# Nucleo.net
KiCad netlist of a schematic drawn in Altium Designer
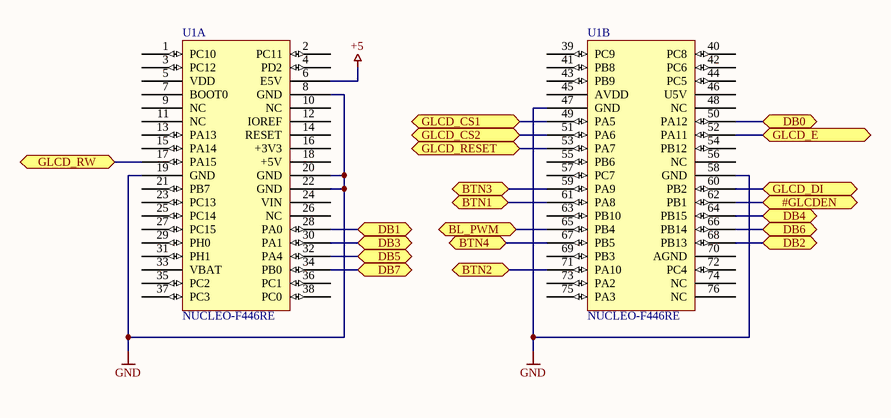
[diagram p0: Nucleo.SchDoc]

(export (version "E")
  (design (tool "Eeschema 10.0.6"))
  (components
    (comp (ref "U1")
      (value "NUCLEO-F446RE")
      (footprint "FP_NUCLEO-64_2x20")
      (libsource (lib "hallglib") (part "NUCLEO-F446RE"))
    )
  )
  (nets
    (net (code "1") (name "+5") (class "Default")
      (node (ref "U1") (pin "6") (pinfunction "E5V_6") (pintype "power_in"))
    )
    (net (code "2") (name "/#GLCDEN") (class "Default")
      (node (ref "U1") (pin "62") (pinfunction "PB1_62") (pintype "bidirectional"))
    )
    (net (code "3") (name "/BL_PWM") (class "Default")
      (node (ref "U1") (pin "65") (pinfunction "PB4_65") (pintype "bidirectional"))
    )
    (net (code "4") (name "/BTN1") (class "Default")
      (node (ref "U1") (pin "61") (pinfunction "PA8_61") (pintype "bidirectional"))
    )
    (net (code "5") (name "/BTN2") (class "Default")
      (node (ref "U1") (pin "71") (pinfunction "PA10_71") (pintype "bidirectional"))
    )
    (net (code "6") (name "/BTN3") (class "Default")
      (node (ref "U1") (pin "59") (pinfunction "PA9_59") (pintype "bidirectional"))
    )
    (net (code "7") (name "/BTN4") (class "Default")
      (node (ref "U1") (pin "67") (pinfunction "PB5_67") (pintype "bidirectional"))
    )
    (net (code "8") (name "/DB0") (class "Default")
      (node (ref "U1") (pin "50") (pinfunction "PA12_50") (pintype "bidirectional"))
    )
    (net (code "9") (name "/DB1") (class "Default")
      (node (ref "U1") (pin "28") (pinfunction "PA0_28") (pintype "bidirectional"))
    )
    (net (code "10") (name "/DB2") (class "Default")
      (node (ref "U1") (pin "68") (pinfunction "PB13_68") (pintype "bidirectional"))
    )
    (net (code "11") (name "/DB3") (class "Default")
      (node (ref "U1") (pin "30") (pinfunction "PA1_30") (pintype "bidirectional"))
    )
    (net (code "12") (name "/DB4") (class "Default")
      (node (ref "U1") (pin "64") (pinfunction "PB15_64") (pintype "bidirectional"))
    )
    (net (code "13") (name "/DB5") (class "Default")
      (node (ref "U1") (pin "32") (pinfunction "PA4_32") (pintype "bidirectional"))
    )
    (net (code "14") (name "/DB6") (class "Default")
      (node (ref "U1") (pin "66") (pinfunction "PB14_66") (pintype "bidirectional"))
    )
    (net (code "15") (name "/DB7") (class "Default")
      (node (ref "U1") (pin "34") (pinfunction "PB0_34") (pintype "bidirectional"))
    )
    (net (code "16") (name "/GLCD_CS1") (class "Default")
      (node (ref "U1") (pin "49") (pinfunction "PA5_49") (pintype "bidirectional"))
    )
    (net (code "17") (name "/GLCD_CS2") (class "Default")
      (node (ref "U1") (pin "51") (pinfunction "PA6_51") (pintype "bidirectional"))
    )
    (net (code "18") (name "/GLCD_DI") (class "Default")
      (node (ref "U1") (pin "60") (pinfunction "PB2_60") (pintype "bidirectional"))
    )
    (net (code "19") (name "/GLCD_E") (class "Default")
      (node (ref "U1") (pin "52") (pinfunction "PA11_52") (pintype "bidirectional"))
    )
    (net (code "20") (name "/GLCD_RESET") (class "Default")
      (node (ref "U1") (pin "53") (pinfunction "PA7_53") (pintype "bidirectional"))
    )
    (net (code "21") (name "/GLCD_RW") (class "Default")
      (node (ref "U1") (pin "17") (pinfunction "PA15_17") (pintype "bidirectional"))
    )
    (net (code "22") (name "GND") (class "Default")
      (node (ref "U1") (pin "19") (pinfunction "GND_19") (pintype "passive"))
      (node (ref "U1") (pin "20") (pinfunction "GND_20") (pintype "passive"))
      (node (ref "U1") (pin "22") (pinfunction "GND_22") (pintype "passive"))
      (node (ref "U1") (pin "47") (pinfunction "GND_47") (pintype "passive"))
      (node (ref "U1") (pin "58") (pinfunction "GND_58") (pintype "passive"))
      (node (ref "U1") (pin "8") (pinfunction "GND_8") (pintype "passive"))
    )
    (net (code "23") (name "unconnected-(U1A-+3V3-Pad16)") (class "Default")
      (node (ref "U1") (pin "16") (pinfunction "+3V3_16") (pintype "power_in"))
    )
    (net (code "24") (name "unconnected-(U1A-+5V-Pad18)") (class "Default")
      (node (ref "U1") (pin "18") (pinfunction "+5V_18") (pintype "power_in"))
    )
    (net (code "25") (name "unconnected-(U1A-BOOT0-Pad7)") (class "Default")
      (node (ref "U1") (pin "7") (pinfunction "BOOT0_7") (pintype "passive"))
    )
    (net (code "26") (name "unconnected-(U1A-IOREF-Pad12)") (class "Default")
      (node (ref "U1") (pin "12") (pinfunction "IOREF_12") (pintype "passive"))
    )
    (net (code "27") (name "unconnected-(U1A-NC-Pad9)") (class "Default")
      (node (ref "U1") (pin "9") (pinfunction "NC_9") (pintype "passive"))
    )
    (net (code "28") (name "unconnected-(U1A-NC-Pad10)") (class "Default")
      (node (ref "U1") (pin "10") (pinfunction "NC_10") (pintype "passive"))
    )
    (net (code "29") (name "unconnected-(U1A-NC-Pad11)") (class "Default")
      (node (ref "U1") (pin "11") (pinfunction "NC_11") (pintype "passive"))
    )
    (net (code "30") (name "unconnected-(U1A-NC-Pad26)") (class "Default")
      (node (ref "U1") (pin "26") (pinfunction "NC_26") (pintype "passive"))
    )
    (net (code "31") (name "unconnected-(U1A-PA13-Pad13)") (class "Default")
      (node (ref "U1") (pin "13") (pinfunction "PA13_13") (pintype "bidirectional"))
    )
    (net (code "32") (name "unconnected-(U1A-PA14-Pad15)") (class "Default")
      (node (ref "U1") (pin "15") (pinfunction "PA14_15") (pintype "bidirectional"))
    )
    (net (code "33") (name "unconnected-(U1A-PB7-Pad21)") (class "Default")
      (node (ref "U1") (pin "21") (pinfunction "PB7_21") (pintype "bidirectional"))
    )
    (net (code "34") (name "unconnected-(U1A-PC0-Pad38)") (class "Default")
      (node (ref "U1") (pin "38") (pinfunction "PC0_38") (pintype "bidirectional"))
    )
    (net (code "35") (name "unconnected-(U1A-PC1-Pad36)") (class "Default")
      (node (ref "U1") (pin "36") (pinfunction "PC1_36") (pintype "bidirectional"))
    )
    (net (code "36") (name "unconnected-(U1A-PC2-Pad35)") (class "Default")
      (node (ref "U1") (pin "35") (pinfunction "PC2_35") (pintype "bidirectional"))
    )
    (net (code "37") (name "unconnected-(U1A-PC3-Pad37)") (class "Default")
      (node (ref "U1") (pin "37") (pinfunction "PC3_37") (pintype "bidirectional"))
    )
    (net (code "38") (name "unconnected-(U1A-PC10-Pad1)") (class "Default")
      (node (ref "U1") (pin "1") (pinfunction "PC10_1") (pintype "bidirectional"))
    )
    (net (code "39") (name "unconnected-(U1A-PC11-Pad2)") (class "Default")
      (node (ref "U1") (pin "2") (pinfunction "PC11_2") (pintype "bidirectional"))
    )
    (net (code "40") (name "unconnected-(U1A-PC12-Pad3)") (class "Default")
      (node (ref "U1") (pin "3") (pinfunction "PC12_3") (pintype "bidirectional"))
    )
    (net (code "41") (name "unconnected-(U1A-PC13-Pad23)") (class "Default")
      (node (ref "U1") (pin "23") (pinfunction "PC13_23") (pintype "bidirectional"))
    )
    (net (code "42") (name "unconnected-(U1A-PC14-Pad25)") (class "Default")
      (node (ref "U1") (pin "25") (pinfunction "PC14_25") (pintype "bidirectional"))
    )
    (net (code "43") (name "unconnected-(U1A-PC15-Pad27)") (class "Default")
      (node (ref "U1") (pin "27") (pinfunction "PC15_27") (pintype "bidirectional"))
    )
    (net (code "44") (name "unconnected-(U1A-PD2-Pad4)") (class "Default")
      (node (ref "U1") (pin "4") (pinfunction "PD2_4") (pintype "bidirectional"))
    )
    (net (code "45") (name "unconnected-(U1A-PH0-Pad29)") (class "Default")
      (node (ref "U1") (pin "29") (pinfunction "PH0_29") (pintype "bidirectional"))
    )
    (net (code "46") (name "unconnected-(U1A-PH1-Pad31)") (class "Default")
      (node (ref "U1") (pin "31") (pinfunction "PH1_31") (pintype "bidirectional"))
    )
    (net (code "47") (name "unconnected-(U1A-RESET-Pad14)") (class "Default")
      (node (ref "U1") (pin "14") (pinfunction "RESET_14") (pintype "passive"))
    )
    (net (code "48") (name "unconnected-(U1A-VBAT-Pad33)") (class "Default")
      (node (ref "U1") (pin "33") (pinfunction "VBAT_33") (pintype "power_in"))
    )
    (net (code "49") (name "unconnected-(U1A-VDD-Pad5)") (class "Default")
      (node (ref "U1") (pin "5") (pinfunction "VDD_5") (pintype "power_in"))
    )
    (net (code "50") (name "unconnected-(U1A-VIN-Pad24)") (class "Default")
      (node (ref "U1") (pin "24") (pinfunction "VIN_24") (pintype "power_in"))
    )
    (net (code "51") (name "unconnected-(U1B-AGND-Pad70)") (class "Default")
      (node (ref "U1") (pin "70") (pinfunction "AGND_70") (pintype "passive"))
    )
    (net (code "52") (name "unconnected-(U1B-AVDD-Pad45)") (class "Default")
      (node (ref "U1") (pin "45") (pinfunction "AVDD_45") (pintype "power_in"))
    )
    (net (code "53") (name "unconnected-(U1B-NC-Pad48)") (class "Default")
      (node (ref "U1") (pin "48") (pinfunction "NC_48") (pintype "passive"))
    )
    (net (code "54") (name "unconnected-(U1B-NC-Pad56)") (class "Default")
      (node (ref "U1") (pin "56") (pinfunction "NC_56") (pintype "passive"))
    )
    (net (code "55") (name "unconnected-(U1B-NC-Pad74)") (class "Default")
      (node (ref "U1") (pin "74") (pinfunction "NC_74") (pintype "passive"))
    )
    (net (code "56") (name "unconnected-(U1B-NC-Pad76)") (class "Default")
      (node (ref "U1") (pin "76") (pinfunction "NC_76") (pintype "passive"))
    )
    (net (code "57") (name "unconnected-(U1B-PA2-Pad73)") (class "Default")
      (node (ref "U1") (pin "73") (pinfunction "PA2_73") (pintype "bidirectional"))
    )
    (net (code "58") (name "unconnected-(U1B-PA3-Pad75)") (class "Default")
      (node (ref "U1") (pin "75") (pinfunction "PA3_75") (pintype "bidirectional"))
    )
    (net (code "59") (name "unconnected-(U1B-PB3-Pad69)") (class "Default")
      (node (ref "U1") (pin "69") (pinfunction "PB3_69") (pintype "bidirectional"))
    )
    (net (code "60") (name "unconnected-(U1B-PB6-Pad55)") (class "Default")
      (node (ref "U1") (pin "55") (pinfunction "PB6_55") (pintype "bidirectional"))
    )
    (net (code "61") (name "unconnected-(U1B-PB8-Pad41)") (class "Default")
      (node (ref "U1") (pin "41") (pinfunction "PB8_41") (pintype "bidirectional"))
    )
    (net (code "62") (name "unconnected-(U1B-PB9-Pad43)") (class "Default")
      (node (ref "U1") (pin "43") (pinfunction "PB9_43") (pintype "bidirectional"))
    )
    (net (code "63") (name "unconnected-(U1B-PB10-Pad63)") (class "Default")
      (node (ref "U1") (pin "63") (pinfunction "PB10_63") (pintype "bidirectional"))
    )
    (net (code "64") (name "unconnected-(U1B-PB12-Pad54)") (class "Default")
      (node (ref "U1") (pin "54") (pinfunction "PB12_54") (pintype "bidirectional"))
    )
    (net (code "65") (name "unconnected-(U1B-PC4-Pad72)") (class "Default")
      (node (ref "U1") (pin "72") (pinfunction "PC4_72") (pintype "bidirectional"))
    )
    (net (code "66") (name "unconnected-(U1B-PC5-Pad44)") (class "Default")
      (node (ref "U1") (pin "44") (pinfunction "PC5_44") (pintype "bidirectional"))
    )
    (net (code "67") (name "unconnected-(U1B-PC6-Pad42)") (class "Default")
      (node (ref "U1") (pin "42") (pinfunction "PC6_42") (pintype "bidirectional"))
    )
    (net (code "68") (name "unconnected-(U1B-PC7-Pad57)") (class "Default")
      (node (ref "U1") (pin "57") (pinfunction "PC7_57") (pintype "bidirectional"))
    )
    (net (code "69") (name "unconnected-(U1B-PC8-Pad40)") (class "Default")
      (node (ref "U1") (pin "40") (pinfunction "PC8_40") (pintype "bidirectional"))
    )
    (net (code "70") (name "unconnected-(U1B-PC9-Pad39)") (class "Default")
      (node (ref "U1") (pin "39") (pinfunction "PC9_39") (pintype "bidirectional"))
    )
    (net (code "71") (name "unconnected-(U1B-U5V-Pad46)") (class "Default")
      (node (ref "U1") (pin "46") (pinfunction "U5V_46") (pintype "power_in"))
    )
  )
)
